# BIRDS3_-Xpanel_FM_Uguisu_v1_1.net
KiCad netlist of a schematic drawn in EAGLE
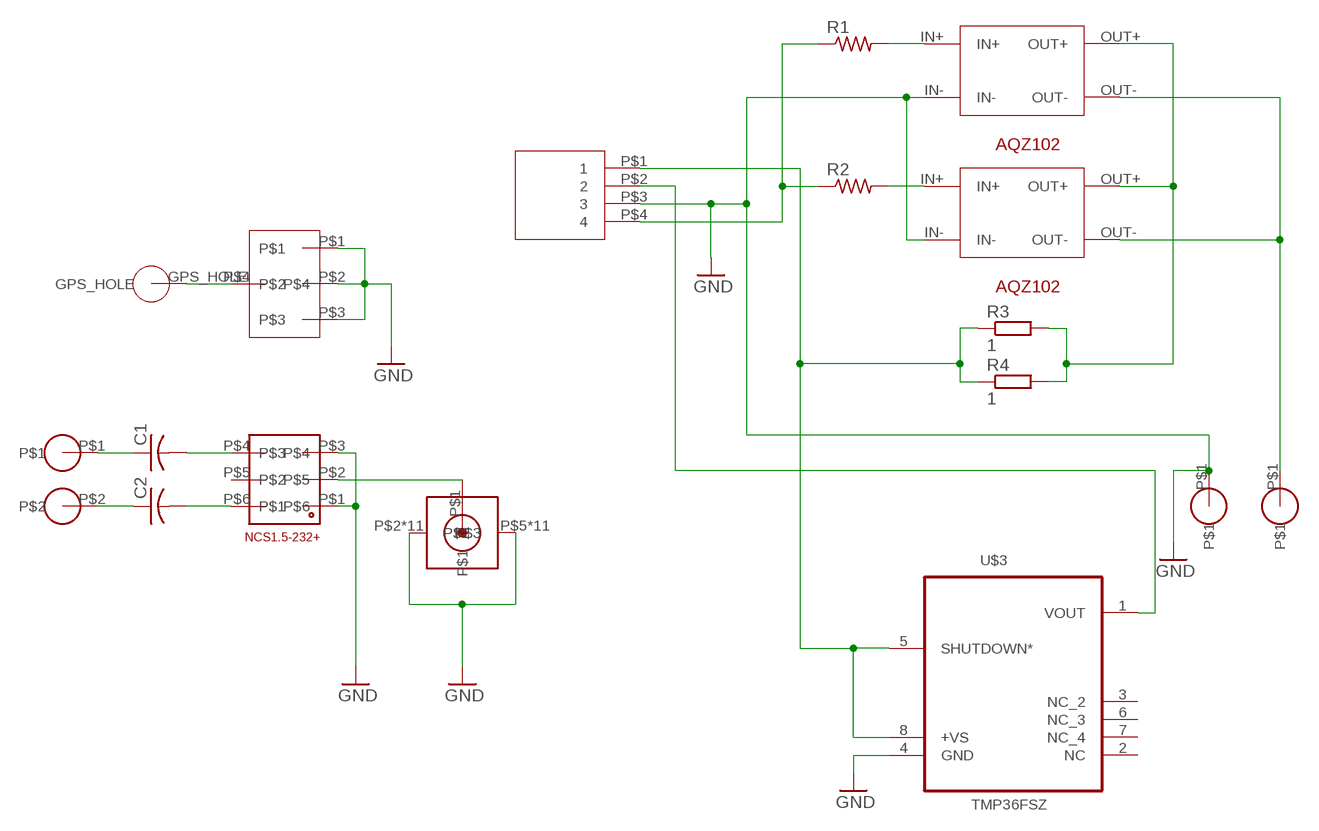
[diagram p0: schematic, sheet 1]

(export (version "E")
  (design (tool "Eeschema 10.0.6"))
  (components
    (comp (ref "142_0711_1")
      (value "SMA_142_0711_301")
      (footprint "eagle-import:SMA_142_0711_301")
      (libsource (lib "eagle-import") (part "SMA_142_0711_301"))
    )
    (comp (ref "C1")
      (value "C-USC1608")
      (footprint "eagle-import:C1608")
      (libsource (lib "eagle-import") (part "C-USC1608"))
    )
    (comp (ref "C2")
      (value "C-USC1608")
      (footprint "eagle-import:C1608")
      (libsource (lib "eagle-import") (part "C-USC1608"))
    )
    (comp (ref "GPS1")
      (value "GPS_HOLE")
      (footprint "eagle-import:GPS_HOLE")
      (libsource (lib "eagle-import") (part "GPS_HOLE"))
    )
    (comp (ref "K1")
      (value "DIODE_X")
      (footprint "eagle-import:DIOD_X")
      (libsource (lib "eagle-import") (part "DIODE_X"))
    )
    (comp (ref "K2")
      (value "DIODE_X")
      (footprint "eagle-import:DIOD_X")
      (libsource (lib "eagle-import") (part "DIODE_X"))
    )
    (comp (ref "MMCX1")
      (value "MMCX_GPS")
      (footprint "eagle-import:MMCX_GPS")
      (libsource (lib "eagle-import") (part "MMCX_GPS"))
    )
    (comp (ref "NCS1")
      (value "NCS1.5-232+")
      (footprint "eagle-import:NCS1.5-232+")
      (libsource (lib "eagle-import") (part "NCS1.5-232+"))
    )
    (comp (ref "PRE1")
      (value "FOR_DIPOLE")
      (footprint "eagle-import:FOR_DIPOLE")
      (libsource (lib "eagle-import") (part "FOR_DIPOLE"))
    )
    (comp (ref "R1")
      (value "R-US_R0402")
      (footprint "eagle-import:R0402")
      (libsource (lib "eagle-import") (part "R-US_R0402"))
    )
    (comp (ref "R2")
      (value "R-US_R0402")
      (footprint "eagle-import:R0402")
      (libsource (lib "eagle-import") (part "R-US_R0402"))
    )
    (comp (ref "R3")
      (value "1")
      (footprint "eagle-import:R1218")
      (libsource (lib "eagle-import") (part "R-EU_R1218"))
    )
    (comp (ref "R4")
      (value "1")
      (footprint "eagle-import:R1218")
      (libsource (lib "eagle-import") (part "R-EU_R1218"))
    )
    (comp (ref "U$1")
      (value "NICR_HOLE")
      (footprint "eagle-import:NICR_HOLE")
      (libsource (lib "eagle-import") (part "NICR_HOLE"))
    )
    (comp (ref "U$2")
      (value "4PIN_HEADER")
      (footprint "eagle-import:4PIN_HEADER")
      (libsource (lib "eagle-import") (part "4PIN_HEADER"))
    )
    (comp (ref "U$3")
      (value "TMP36FSZ")
      (footprint "eagle-import:SOIC_N")
      (libsource (lib "eagle-import") (part "TMP36FSZ"))
    )
    (comp (ref "U$4")
      (value "NICR_HOLE")
      (footprint "eagle-import:NICR_HOLE")
      (libsource (lib "eagle-import") (part "NICR_HOLE"))
    )
  )
  (nets
    (net (code "1") (name "GND") (class "Default")
      (node (ref "142_0711_1") (pin "P$10") (pinfunction "P$3_P$10") (pintype "bidirectional"))
      (node (ref "142_0711_1") (pin "P$11") (pinfunction "P$3_P$11") (pintype "bidirectional"))
      (node (ref "142_0711_1") (pin "P$12") (pinfunction "P$2_P$12") (pintype "bidirectional"))
      (node (ref "142_0711_1") (pin "P$13") (pinfunction "P$2_P$13") (pintype "bidirectional"))
      (node (ref "142_0711_1") (pin "P$14") (pinfunction "P$3_P$14") (pintype "bidirectional"))
      (node (ref "142_0711_1") (pin "P$15") (pinfunction "P$3_P$15") (pintype "bidirectional"))
      (node (ref "142_0711_1") (pin "P$16") (pinfunction "P$2_P$16") (pintype "bidirectional"))
      (node (ref "142_0711_1") (pin "P$17") (pinfunction "P$2_P$17") (pintype "bidirectional"))
      (node (ref "142_0711_1") (pin "P$18") (pinfunction "P$3_P$18") (pintype "bidirectional"))
      (node (ref "142_0711_1") (pin "P$19") (pinfunction "P$3_P$19") (pintype "bidirectional"))
      (node (ref "142_0711_1") (pin "P$2") (pinfunction "P$2_P$2") (pintype "bidirectional"))
      (node (ref "142_0711_1") (pin "P$20") (pinfunction "P$2_P$20") (pintype "bidirectional"))
      (node (ref "142_0711_1") (pin "P$21") (pinfunction "P$2_P$21") (pintype "bidirectional"))
      (node (ref "142_0711_1") (pin "P$22") (pinfunction "P$3_P$22") (pintype "bidirectional"))
      (node (ref "142_0711_1") (pin "P$23") (pinfunction "P$3_P$23") (pintype "bidirectional"))
      (node (ref "142_0711_1") (pin "P$3") (pinfunction "P$2_P$3") (pintype "bidirectional"))
      (node (ref "142_0711_1") (pin "P$4") (pinfunction "P$2_P$4") (pintype "bidirectional"))
      (node (ref "142_0711_1") (pin "P$5") (pinfunction "P$3_P$5") (pintype "bidirectional"))
      (node (ref "142_0711_1") (pin "P$6") (pinfunction "P$3_P$6") (pintype "bidirectional"))
      (node (ref "142_0711_1") (pin "P$7") (pinfunction "P$3_P$7") (pintype "bidirectional"))
      (node (ref "142_0711_1") (pin "P$8") (pinfunction "P$2_P$8") (pintype "bidirectional"))
      (node (ref "142_0711_1") (pin "P$9") (pinfunction "P$2_P$9") (pintype "bidirectional"))
      (node (ref "K1") (pin "IN-") (pinfunction "IN-_IN-") (pintype "bidirectional"))
      (node (ref "K2") (pin "IN-") (pinfunction "IN-_IN-") (pintype "bidirectional"))
      (node (ref "MMCX1") (pin "P$1") (pinfunction "P$1_P$1") (pintype "bidirectional"))
      (node (ref "MMCX1") (pin "P$2") (pinfunction "P$2_P$2") (pintype "bidirectional"))
      (node (ref "MMCX1") (pin "P$3") (pinfunction "P$3_P$3") (pintype "bidirectional"))
      (node (ref "NCS1") (pin "P$1") (pinfunction "P$1_P$1") (pintype "bidirectional"))
      (node (ref "NCS1") (pin "P$3") (pinfunction "P$3_P$3") (pintype "bidirectional"))
      (node (ref "U$2") (pin "P$3") (pinfunction "3_P$3") (pintype "bidirectional"))
      (node (ref "U$3") (pin "4") (pinfunction "GND_4") (pintype "passive"))
      (node (ref "U$4") (pin "P$1") (pinfunction "P$1_P$1") (pintype "bidirectional"))
    )
    (net (code "2") (name "Net-(142_0711_1-PadP$1)") (class "Default")
      (node (ref "142_0711_1") (pin "P$1") (pinfunction "P$1_P$1") (pintype "bidirectional"))
      (node (ref "NCS1") (pin "P$2") (pinfunction "P$2_P$2") (pintype "bidirectional"))
    )
    (net (code "3") (name "Net-(C1-Pad1)") (class "Default")
      (node (ref "C1") (pin "1") (pinfunction "1_1") (pintype "passive"))
      (node (ref "PRE1") (pin "P$1") (pinfunction "P$1_P$1") (pintype "bidirectional"))
    )
    (net (code "4") (name "Net-(C1-Pad2)") (class "Default")
      (node (ref "C1") (pin "2") (pinfunction "2_2") (pintype "passive"))
      (node (ref "NCS1") (pin "P$4") (pinfunction "P$4_P$4") (pintype "bidirectional"))
    )
    (net (code "5") (name "Net-(C2-Pad1)") (class "Default")
      (node (ref "C2") (pin "1") (pinfunction "1_1") (pintype "passive"))
      (node (ref "PRE1") (pin "P$2") (pinfunction "P$2_P$2") (pintype "bidirectional"))
    )
    (net (code "6") (name "Net-(C2-Pad2)") (class "Default")
      (node (ref "C2") (pin "2") (pinfunction "2_2") (pintype "passive"))
      (node (ref "NCS1") (pin "P$6") (pinfunction "P$6_P$6") (pintype "bidirectional"))
    )
    (net (code "7") (name "Net-(GPS1-PadGPS_HOLE)") (class "Default")
      (node (ref "GPS1") (pin "GPS_HOLE") (pinfunction "GPS_HOLE_GPS_HOLE") (pintype "bidirectional"))
      (node (ref "MMCX1") (pin "P$4") (pinfunction "P$4_P$4") (pintype "bidirectional"))
    )
    (net (code "8") (name "Net-(K1-PadIN+)") (class "Default")
      (node (ref "K1") (pin "IN+") (pinfunction "IN+_IN+") (pintype "bidirectional"))
      (node (ref "R2") (pin "2") (pinfunction "2_2") (pintype "passive"))
    )
    (net (code "9") (name "Net-(K1-PadOUT+)") (class "Default")
      (node (ref "K1") (pin "OUT+") (pinfunction "OUT+_OUT+") (pintype "bidirectional"))
      (node (ref "K2") (pin "OUT+") (pinfunction "OUT+_OUT+") (pintype "bidirectional"))
      (node (ref "R3") (pin "2") (pinfunction "2_2") (pintype "passive"))
      (node (ref "R4") (pin "2") (pinfunction "2_2") (pintype "passive"))
    )
    (net (code "10") (name "Net-(K1-PadOUT-)") (class "Default")
      (node (ref "K1") (pin "OUT-") (pinfunction "OUT-_OUT-") (pintype "bidirectional"))
      (node (ref "K2") (pin "OUT-") (pinfunction "OUT-_OUT-") (pintype "bidirectional"))
      (node (ref "U$1") (pin "P$1") (pinfunction "P$1_P$1") (pintype "bidirectional"))
    )
    (net (code "11") (name "Net-(K2-PadIN+)") (class "Default")
      (node (ref "K2") (pin "IN+") (pinfunction "IN+_IN+") (pintype "bidirectional"))
      (node (ref "R1") (pin "2") (pinfunction "2_2") (pintype "passive"))
    )
    (net (code "12") (name "Net-(U$2-1)") (class "Default")
      (node (ref "R3") (pin "1") (pinfunction "1_1") (pintype "passive"))
      (node (ref "R4") (pin "1") (pinfunction "1_1") (pintype "passive"))
      (node (ref "U$2") (pin "P$1") (pinfunction "1_P$1") (pintype "bidirectional"))
      (node (ref "U$3") (pin "5") (pinfunction "SHUTDOWN*_5") (pintype "passive"))
      (node (ref "U$3") (pin "8") (pinfunction "+VS_8") (pintype "power_in"))
    )
    (net (code "13") (name "Net-(U$2-2)") (class "Default")
      (node (ref "U$2") (pin "P$2") (pinfunction "2_P$2") (pintype "bidirectional"))
      (node (ref "U$3") (pin "1") (pinfunction "VOUT_1") (pintype "passive"))
    )
    (net (code "14") (name "Net-(U$2-4)") (class "Default")
      (node (ref "R1") (pin "1") (pinfunction "1_1") (pintype "passive"))
      (node (ref "R2") (pin "1") (pinfunction "1_1") (pintype "passive"))
      (node (ref "U$2") (pin "P$4") (pinfunction "4_P$4") (pintype "bidirectional"))
    )
    (net (code "15") (name "unconnected-(NCS1-PadP$5)") (class "Default")
      (node (ref "NCS1") (pin "P$5") (pinfunction "P$5_P$5") (pintype "bidirectional"))
    )
    (net (code "16") (name "unconnected-(U$3-NC-Pad2)") (class "Default")
      (node (ref "U$3") (pin "2") (pinfunction "NC_2") (pintype "passive"))
    )
    (net (code "17") (name "unconnected-(U$3-NC_2-Pad3)") (class "Default")
      (node (ref "U$3") (pin "3") (pinfunction "NC_2_3") (pintype "passive"))
    )
    (net (code "18") (name "unconnected-(U$3-NC_3-Pad6)") (class "Default")
      (node (ref "U$3") (pin "6") (pinfunction "NC_3_6") (pintype "passive"))
    )
    (net (code "19") (name "unconnected-(U$3-NC_4-Pad7)") (class "Default")
      (node (ref "U$3") (pin "7") (pinfunction "NC_4_7") (pintype "passive"))
    )
  )
)
